# USB-DMX-ISOLATED.net
KiCad netlist of a schematic drawn in EAGLE
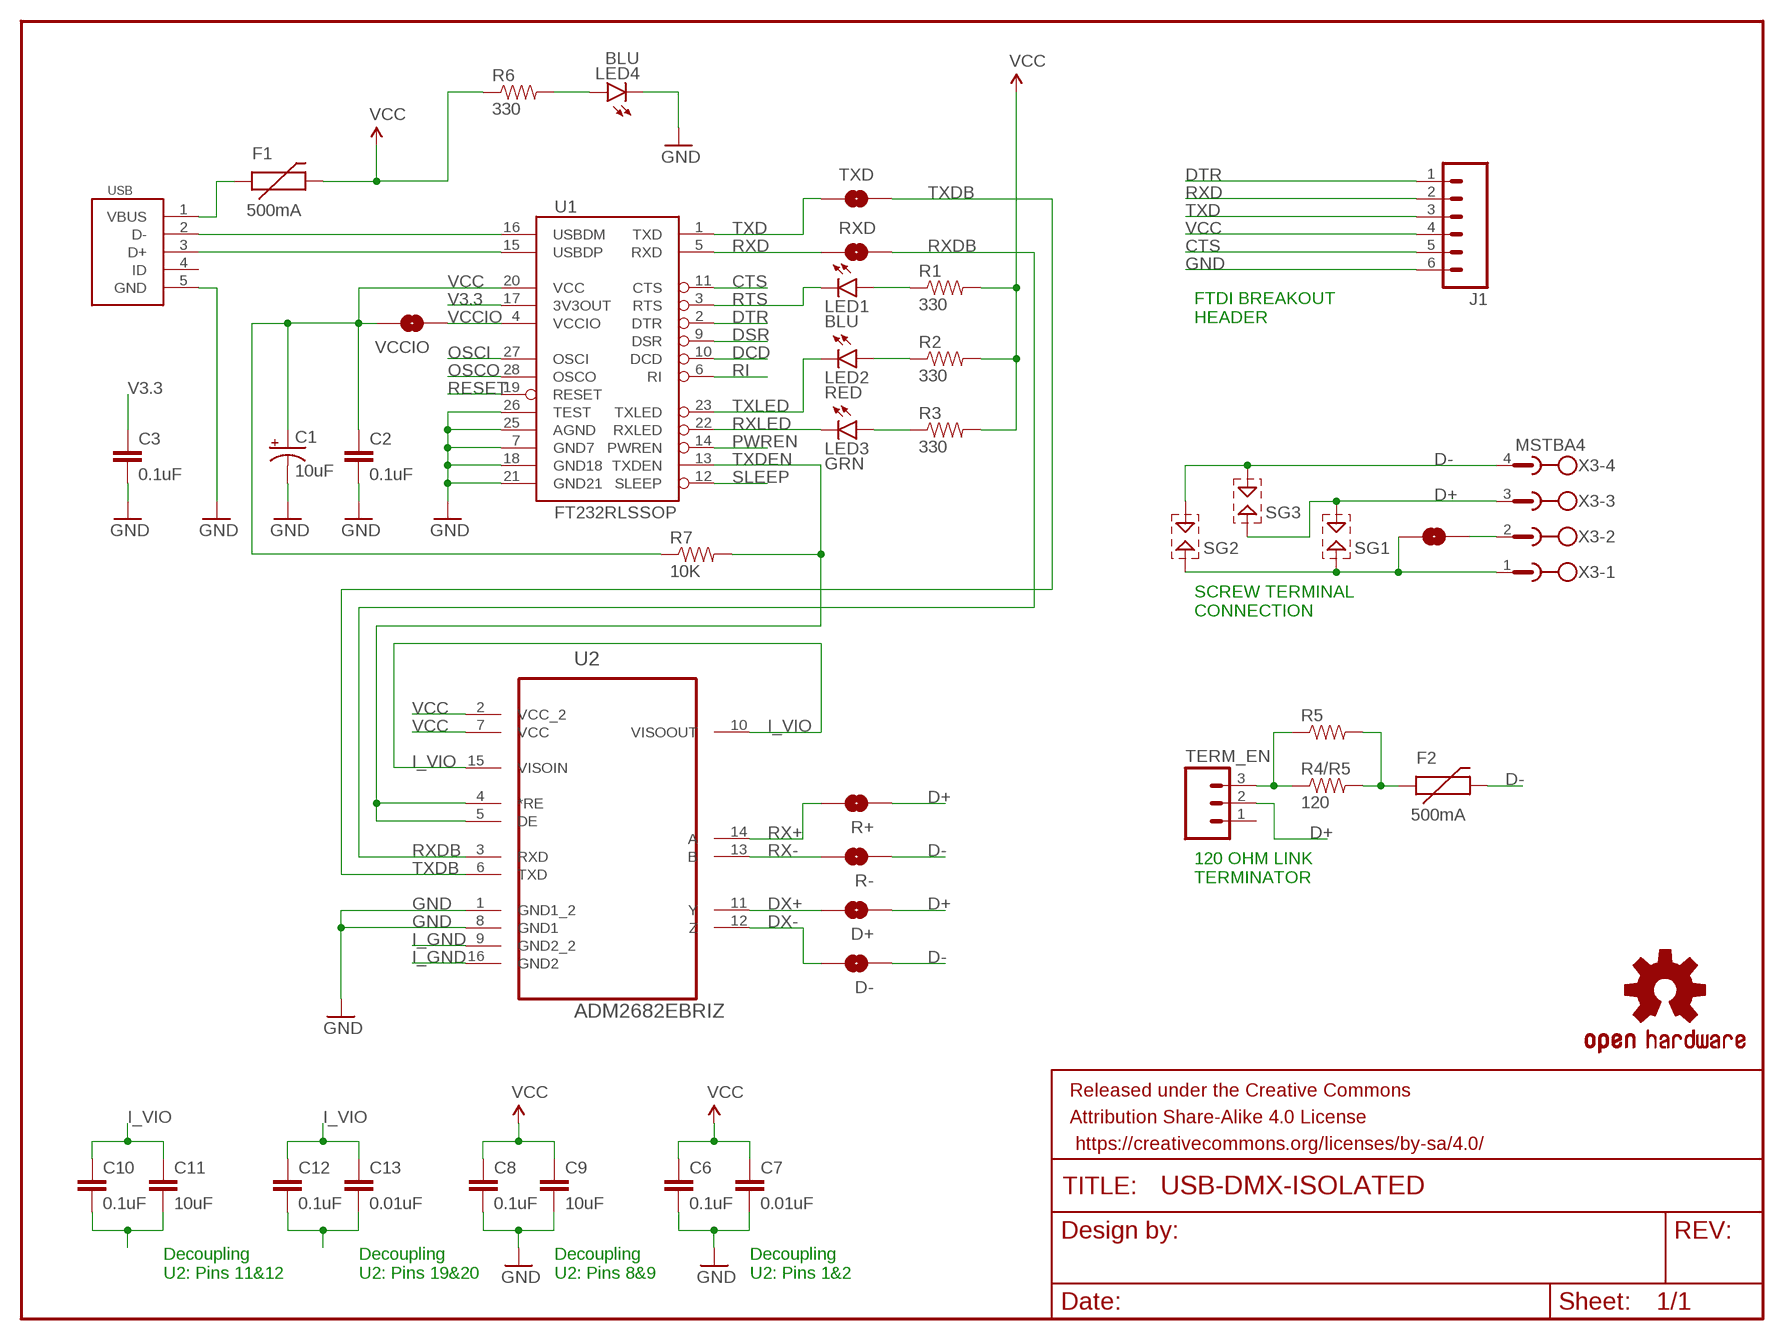
[diagram p0: schematic, sheet 1]

(export (version "E")
  (design (tool "Eeschema 10.0.6"))
  (components
    (comp (ref "C1")
      (value "10uF")
      (footprint "eagle-import:EIA3216")
      (libsource (lib "eagle-import") (part "10UF-16V-10%(TANT)"))
    )
    (comp (ref "C2")
      (value "0.1uF")
      (footprint "eagle-import:1206")
      (libsource (lib "eagle-import") (part "CAP1206"))
    )
    (comp (ref "C3")
      (value "0.1uF")
      (footprint "eagle-import:1206")
      (libsource (lib "eagle-import") (part "CAP1206"))
    )
    (comp (ref "C6")
      (value "0.1uF")
      (footprint "eagle-import:1206")
      (libsource (lib "eagle-import") (part "CAP1206"))
    )
    (comp (ref "C7")
      (value "0.01uF")
      (footprint "eagle-import:1206")
      (libsource (lib "eagle-import") (part "CAP1206"))
    )
    (comp (ref "C8")
      (value "0.1uF")
      (footprint "eagle-import:1206")
      (libsource (lib "eagle-import") (part "CAP1206"))
    )
    (comp (ref "C9")
      (value "10uF")
      (footprint "eagle-import:1206")
      (libsource (lib "eagle-import") (part "CAP1206"))
    )
    (comp (ref "C10")
      (value "0.1uF")
      (footprint "eagle-import:1206")
      (libsource (lib "eagle-import") (part "CAP1206"))
    )
    (comp (ref "C11")
      (value "10uF")
      (footprint "eagle-import:1206")
      (libsource (lib "eagle-import") (part "CAP1206"))
    )
    (comp (ref "C12")
      (value "0.1uF")
      (footprint "eagle-import:1206")
      (libsource (lib "eagle-import") (part "CAP1206"))
    )
    (comp (ref "C13")
      (value "0.01uF")
      (footprint "eagle-import:1206")
      (libsource (lib "eagle-import") (part "CAP1206"))
    )
    (comp (ref "D+")
      (value "SOLDERJUMPERTRACE")
      (footprint "eagle-import:SJ_2S-TRACE")
      (libsource (lib "eagle-import") (part "SOLDERJUMPERTRACE"))
    )
    (comp (ref "D-")
      (value "SOLDERJUMPERTRACE")
      (footprint "eagle-import:SJ_2S-TRACE")
      (libsource (lib "eagle-import") (part "SOLDERJUMPERTRACE"))
    )
    (comp (ref "F1")
      (value "500mA")
      (footprint "eagle-import:PTC-1206")
      (libsource (lib "eagle-import") (part "PTCSMD"))
    )
    (comp (ref "F2")
      (value "500mA")
      (footprint "eagle-import:PTC-1206")
      (libsource (lib "eagle-import") (part "PTCSMD"))
    )
    (comp (ref "FRAME1")
      (value "FRAME-LETTERNO_PACKAGE")
      (footprint "eagle-import:DUMMY")
      (fields (field (name "DESIGNER") "Nobody"))
      (libsource (lib "eagle-import") (part "FRAME-LETTERNO_PACKAGE"))
    )
    (comp (ref "J1")
      (value "M06LOCK")
      (footprint "eagle-import:1X06_LOCK")
      (libsource (lib "eagle-import") (part "M06LOCK"))
    )
    (comp (ref "LED1")
      (value "BLU")
      (footprint "eagle-import:LED-1206")
      (libsource (lib "eagle-import") (part "LED1206"))
    )
    (comp (ref "LED2")
      (value "RED")
      (footprint "eagle-import:LED-1206")
      (libsource (lib "eagle-import") (part "LED1206"))
    )
    (comp (ref "LED3")
      (value "GRN")
      (footprint "eagle-import:LED-1206")
      (libsource (lib "eagle-import") (part "LED1206"))
    )
    (comp (ref "LED4")
      (value "BLU")
      (footprint "eagle-import:LED-1206")
      (libsource (lib "eagle-import") (part "LED1206"))
    )
    (comp (ref "LOGO1")
      (value "OSHW-LOGOS")
      (footprint "eagle-import:OSHW-LOGO-S")
      (libsource (lib "eagle-import") (part "OSHW-LOGOS"))
    )
    (comp (ref "P2_COM")
      (value "SOLDERJUMPERTRACE")
      (footprint "eagle-import:SJ_2S-TRACE")
      (libsource (lib "eagle-import") (part "SOLDERJUMPERTRACE"))
    )
    (comp (ref "R+")
      (value "SOLDERJUMPERTRACE")
      (footprint "eagle-import:SJ_2S-TRACE")
      (libsource (lib "eagle-import") (part "SOLDERJUMPERTRACE"))
    )
    (comp (ref "R-")
      (value "SOLDERJUMPERTRACE")
      (footprint "eagle-import:SJ_2S-TRACE")
      (libsource (lib "eagle-import") (part "SOLDERJUMPERTRACE"))
    )
    (comp (ref "R1")
      (value "330")
      (footprint "eagle-import:1206")
      (libsource (lib "eagle-import") (part "RESISTOR1206"))
    )
    (comp (ref "R2")
      (value "330")
      (footprint "eagle-import:1206")
      (libsource (lib "eagle-import") (part "RESISTOR1206"))
    )
    (comp (ref "R3")
      (value "330")
      (footprint "eagle-import:1206")
      (libsource (lib "eagle-import") (part "RESISTOR1206"))
    )
    (comp (ref "R4/R5")
      (value "120")
      (footprint "eagle-import:1206")
      (libsource (lib "eagle-import") (part "RESISTOR1206"))
    )
    (comp (ref "R5")
      (value "RESISTORPTH-1W")
      (footprint "eagle-import:AXIAL-0.6")
      (libsource (lib "eagle-import") (part "RESISTORPTH-1W"))
    )
    (comp (ref "R6")
      (value "330")
      (footprint "eagle-import:1206")
      (libsource (lib "eagle-import") (part "RESISTOR1206"))
    )
    (comp (ref "R7")
      (value "10K")
      (footprint "eagle-import:1206")
      (libsource (lib "eagle-import") (part "RESISTOR1206"))
    )
    (comp (ref "RXD")
      (value "SOLDERJUMPERTRACE")
      (footprint "eagle-import:SJ_2S-TRACE")
      (libsource (lib "eagle-import") (part "SOLDERJUMPERTRACE"))
    )
    (comp (ref "SG1")
      (value "SPARK-GAP-8")
      (footprint "eagle-import:SPARK-GAP-8")
      (libsource (lib "eagle-import") (part "SPARK-GAP-8"))
    )
    (comp (ref "SG2")
      (value "SPARK-GAP-8")
      (footprint "eagle-import:SPARK-GAP-8")
      (libsource (lib "eagle-import") (part "SPARK-GAP-8"))
    )
    (comp (ref "SG3")
      (value "SPARK-GAP-8")
      (footprint "eagle-import:SPARK-GAP-8")
      (libsource (lib "eagle-import") (part "SPARK-GAP-8"))
    )
    (comp (ref "TERM_EN")
      (value "M03LOCK")
      (footprint "eagle-import:1X03_LOCK")
      (libsource (lib "eagle-import") (part "M03LOCK"))
    )
    (comp (ref "TXD")
      (value "SOLDERJUMPERTRACE")
      (footprint "eagle-import:SJ_2S-TRACE")
      (libsource (lib "eagle-import") (part "SOLDERJUMPERTRACE"))
    )
    (comp (ref "U1")
      (value "FT232RLSSOP")
      (footprint "eagle-import:SSOP28DB")
      (libsource (lib "eagle-import") (part "FT232RLSSOP"))
    )
    (comp (ref "U2")
      (value "ADM2682EBRIZ")
      (footprint "eagle-import:SOIC127P1032X265-16N")
      (libsource (lib "eagle-import") (part "ADM2682EBRIZ"))
    )
    (comp (ref "USB")
      (value "USB-CON-5PIN-105017-0001")
      (footprint "eagle-import:USB-MICRO-MOLEX-105017-0001")
      (libsource (lib "eagle-import") (part "USB-CON-5PIN-105017-0001"))
    )
    (comp (ref "VCCIO")
      (value "SOLDERJUMPERTRACE")
      (footprint "eagle-import:SJ_2S-TRACE")
      (libsource (lib "eagle-import") (part "SOLDERJUMPERTRACE"))
    )
    (comp (ref "X3")
      (value "MSTBA4")
      (footprint "eagle-import:MSTBA4")
      (fields (field (name "MF") "FARNELL") (field (name "MPN") "1757268"))
      (libsource (lib "eagle-import") (part "MSTBA4"))
    )
  )
  (nets
    (net (code "1") (name "/CTS") (class "Default")
      (node (ref "J1") (pin "5") (pinfunction "5_5") (pintype "passive"))
      (node (ref "U1") (pin "11") (pinfunction "CTS_11") (pintype "input"))
    )
    (net (code "2") (name "/D+") (class "Default")
      (node (ref "D+") (pin "1") (pinfunction "1_1") (pintype "passive"))
      (node (ref "R+") (pin "1") (pinfunction "1_1") (pintype "passive"))
      (node (ref "SG1") (pin "1") (pinfunction "1_1") (pintype "passive"))
      (node (ref "SG3") (pin "2") (pinfunction "2_2") (pintype "passive"))
      (node (ref "TERM_EN") (pin "2") (pinfunction "2_2") (pintype "passive"))
      (node (ref "X3") (pin "3") (pinfunction "1_3") (pintype "passive"))
    )
    (net (code "3") (name "/D-") (class "Default")
      (node (ref "D-") (pin "1") (pinfunction "1_1") (pintype "passive"))
      (node (ref "F2") (pin "2") (pinfunction "2_2") (pintype "bidirectional"))
      (node (ref "R-") (pin "1") (pinfunction "1_1") (pintype "passive"))
      (node (ref "SG2") (pin "1") (pinfunction "1_1") (pintype "passive"))
      (node (ref "SG3") (pin "1") (pinfunction "1_1") (pintype "passive"))
      (node (ref "X3") (pin "4") (pinfunction "1_4") (pintype "passive"))
    )
    (net (code "4") (name "/DCD") (class "Default")
      (node (ref "U1") (pin "10") (pinfunction "DCD_10") (pintype "input"))
    )
    (net (code "5") (name "/DSR") (class "Default")
      (node (ref "U1") (pin "9") (pinfunction "DSR_9") (pintype "input"))
    )
    (net (code "6") (name "/DTR") (class "Default")
      (node (ref "J1") (pin "1") (pinfunction "1_1") (pintype "passive"))
      (node (ref "U1") (pin "2") (pinfunction "DTR_2") (pintype "output"))
    )
    (net (code "7") (name "/DX+") (class "Default")
      (node (ref "D+") (pin "2") (pinfunction "2_2") (pintype "passive"))
      (node (ref "U2") (pin "11") (pinfunction "Y_11") (pintype "passive"))
    )
    (net (code "8") (name "/DX-") (class "Default")
      (node (ref "D-") (pin "2") (pinfunction "2_2") (pintype "passive"))
      (node (ref "U2") (pin "12") (pinfunction "Z_12") (pintype "passive"))
    )
    (net (code "9") (name "/I_GND") (class "Default")
      (node (ref "C10") (pin "2") (pinfunction "2_2") (pintype "passive"))
      (node (ref "C11") (pin "2") (pinfunction "2_2") (pintype "passive"))
      (node (ref "C12") (pin "2") (pinfunction "2_2") (pintype "passive"))
      (node (ref "C13") (pin "2") (pinfunction "2_2") (pintype "passive"))
      (node (ref "P2_COM") (pin "1") (pinfunction "1_1") (pintype "passive"))
      (node (ref "SG1") (pin "2") (pinfunction "2_2") (pintype "passive"))
      (node (ref "SG2") (pin "2") (pinfunction "2_2") (pintype "passive"))
      (node (ref "U2") (pin "16") (pinfunction "GND2_16") (pintype "passive"))
      (node (ref "U2") (pin "9") (pinfunction "GND2_2_9") (pintype "passive"))
      (node (ref "X3") (pin "1") (pinfunction "1_1") (pintype "passive"))
    )
    (net (code "10") (name "/I_VIO") (class "Default")
      (node (ref "C10") (pin "1") (pinfunction "1_1") (pintype "passive"))
      (node (ref "C11") (pin "1") (pinfunction "1_1") (pintype "passive"))
      (node (ref "C12") (pin "1") (pinfunction "1_1") (pintype "passive"))
      (node (ref "C13") (pin "1") (pinfunction "1_1") (pintype "passive"))
      (node (ref "U2") (pin "10") (pinfunction "VISOOUT_10") (pintype "passive"))
      (node (ref "U2") (pin "15") (pinfunction "VISOIN_15") (pintype "passive"))
    )
    (net (code "11") (name "/OSCI") (class "Default")
      (node (ref "U1") (pin "27") (pinfunction "OSCI_27") (pintype "input"))
    )
    (net (code "12") (name "/OSCO") (class "Default")
      (node (ref "U1") (pin "28") (pinfunction "OSCO_28") (pintype "output"))
    )
    (net (code "13") (name "/PWREN") (class "Default")
      (node (ref "U1") (pin "14") (pinfunction "PWREN_14") (pintype "input"))
    )
    (net (code "14") (name "/RESET") (class "Default")
      (node (ref "U1") (pin "19") (pinfunction "RESET_19") (pintype "input"))
    )
    (net (code "15") (name "/RI") (class "Default")
      (node (ref "U1") (pin "6") (pinfunction "RI_6") (pintype "input"))
    )
    (net (code "16") (name "/RTS") (class "Default")
      (node (ref "LED1") (pin "C") (pinfunction "C_C") (pintype "passive"))
      (node (ref "U1") (pin "3") (pinfunction "RTS_3") (pintype "output"))
    )
    (net (code "17") (name "/RX+") (class "Default")
      (node (ref "R+") (pin "2") (pinfunction "2_2") (pintype "passive"))
      (node (ref "U2") (pin "14") (pinfunction "A_14") (pintype "passive"))
    )
    (net (code "18") (name "/RX-") (class "Default")
      (node (ref "R-") (pin "2") (pinfunction "2_2") (pintype "passive"))
      (node (ref "U2") (pin "13") (pinfunction "B_13") (pintype "passive"))
    )
    (net (code "19") (name "/RXD") (class "Default")
      (node (ref "J1") (pin "2") (pinfunction "2_2") (pintype "passive"))
      (node (ref "RXD") (pin "1") (pinfunction "1_1") (pintype "passive"))
      (node (ref "U1") (pin "5") (pinfunction "RXD_5") (pintype "input"))
    )
    (net (code "20") (name "/RXDB") (class "Default")
      (node (ref "RXD") (pin "2") (pinfunction "2_2") (pintype "passive"))
      (node (ref "U2") (pin "3") (pinfunction "RXD_3") (pintype "passive"))
    )
    (net (code "21") (name "/RXLED") (class "Default")
      (node (ref "LED3") (pin "C") (pinfunction "C_C") (pintype "passive"))
      (node (ref "U1") (pin "22") (pinfunction "RXLED_22") (pintype "input"))
    )
    (net (code "22") (name "/SLEEP") (class "Default")
      (node (ref "U1") (pin "12") (pinfunction "SLEEP_12") (pintype "input"))
    )
    (net (code "23") (name "/TXD") (class "Default")
      (node (ref "J1") (pin "3") (pinfunction "3_3") (pintype "passive"))
      (node (ref "TXD") (pin "1") (pinfunction "1_1") (pintype "passive"))
      (node (ref "U1") (pin "1") (pinfunction "TXD_1") (pintype "output"))
    )
    (net (code "24") (name "/TXDB") (class "Default")
      (node (ref "TXD") (pin "2") (pinfunction "2_2") (pintype "passive"))
      (node (ref "U2") (pin "6") (pinfunction "TXD_6") (pintype "passive"))
    )
    (net (code "25") (name "/TXDEN") (class "Default")
      (node (ref "R7") (pin "2") (pinfunction "2_2") (pintype "passive"))
      (node (ref "U1") (pin "13") (pinfunction "TXDEN_13") (pintype "input"))
      (node (ref "U2") (pin "4") (pinfunction "*RE_4") (pintype "passive"))
      (node (ref "U2") (pin "5") (pinfunction "DE_5") (pintype "passive"))
    )
    (net (code "26") (name "/TXLED") (class "Default")
      (node (ref "LED2") (pin "C") (pinfunction "C_C") (pintype "passive"))
      (node (ref "U1") (pin "23") (pinfunction "TXLED_23") (pintype "input"))
    )
    (net (code "27") (name "/V3.3") (class "Default")
      (node (ref "C3") (pin "1") (pinfunction "1_1") (pintype "passive"))
      (node (ref "U1") (pin "17") (pinfunction "3V3OUT_17") (pintype "output"))
    )
    (net (code "28") (name "/VCCIO") (class "Default")
      (node (ref "U1") (pin "4") (pinfunction "VCCIO_4") (pintype "power_in"))
      (node (ref "VCCIO") (pin "1") (pinfunction "1_1") (pintype "passive"))
    )
    (net (code "29") (name "GND") (class "Default")
      (node (ref "C1") (pin "C") (pinfunction "-_C") (pintype "passive"))
      (node (ref "C2") (pin "2") (pinfunction "2_2") (pintype "passive"))
      (node (ref "C3") (pin "2") (pinfunction "2_2") (pintype "passive"))
      (node (ref "C6") (pin "2") (pinfunction "2_2") (pintype "passive"))
      (node (ref "C7") (pin "2") (pinfunction "2_2") (pintype "passive"))
      (node (ref "C8") (pin "2") (pinfunction "2_2") (pintype "passive"))
      (node (ref "C9") (pin "2") (pinfunction "2_2") (pintype "passive"))
      (node (ref "J1") (pin "6") (pinfunction "6_6") (pintype "passive"))
      (node (ref "LED4") (pin "C") (pinfunction "C_C") (pintype "passive"))
      (node (ref "U1") (pin "18") (pinfunction "GND18_18") (pintype "power_in"))
      (node (ref "U1") (pin "21") (pinfunction "GND21_21") (pintype "power_in"))
      (node (ref "U1") (pin "25") (pinfunction "AGND_25") (pintype "power_in"))
      (node (ref "U1") (pin "26") (pinfunction "TEST_26") (pintype "input"))
      (node (ref "U1") (pin "7") (pinfunction "GND7_7") (pintype "power_in"))
      (node (ref "U2") (pin "1") (pinfunction "GND1_2_1") (pintype "passive"))
      (node (ref "U2") (pin "8") (pinfunction "GND1_8") (pintype "passive"))
      (node (ref "USB") (pin "5") (pinfunction "GND_5") (pintype "power_in"))
    )
    (net (code "30") (name "Net-(LED1-PadA)") (class "Default")
      (node (ref "LED1") (pin "A") (pinfunction "A_A") (pintype "passive"))
      (node (ref "R1") (pin "1") (pinfunction "1_1") (pintype "passive"))
    )
    (net (code "31") (name "Net-(LED2-PadA)") (class "Default")
      (node (ref "LED2") (pin "A") (pinfunction "A_A") (pintype "passive"))
      (node (ref "R2") (pin "1") (pinfunction "1_1") (pintype "passive"))
    )
    (net (code "32") (name "Net-(LED3-PadA)") (class "Default")
      (node (ref "LED3") (pin "A") (pinfunction "A_A") (pintype "passive"))
      (node (ref "R3") (pin "1") (pinfunction "1_1") (pintype "passive"))
    )
    (net (code "33") (name "Net-(LED4-PadA)") (class "Default")
      (node (ref "LED4") (pin "A") (pinfunction "A_A") (pintype "passive"))
      (node (ref "R6") (pin "2") (pinfunction "2_2") (pintype "passive"))
    )
    (net (code "34") (name "Net-(R5-1)") (class "Default")
      (node (ref "R4/R5") (pin "1") (pinfunction "1_1") (pintype "passive"))
      (node (ref "R5") (pin "P$1") (pinfunction "1_P$1") (pintype "passive"))
      (node (ref "TERM_EN") (pin "3") (pinfunction "3_3") (pintype "passive"))
    )
    (net (code "35") (name "Net-(R5-2)") (class "Default")
      (node (ref "F2") (pin "1") (pinfunction "1_1") (pintype "bidirectional"))
      (node (ref "R4/R5") (pin "2") (pinfunction "2_2") (pintype "passive"))
      (node (ref "R5") (pin "P$2") (pinfunction "2_P$2") (pintype "passive"))
    )
    (net (code "36") (name "Net-(U1-USBDM)") (class "Default")
      (node (ref "U1") (pin "16") (pinfunction "USBDM_16") (pintype "bidirectional"))
      (node (ref "USB") (pin "2") (pinfunction "D-_2") (pintype "bidirectional"))
    )
    (net (code "37") (name "Net-(U1-USBDP)") (class "Default")
      (node (ref "U1") (pin "15") (pinfunction "USBDP_15") (pintype "bidirectional"))
      (node (ref "USB") (pin "3") (pinfunction "D+_3") (pintype "bidirectional"))
    )
    (net (code "38") (name "Net-(USB-VBUS)") (class "Default")
      (node (ref "F1") (pin "1") (pinfunction "1_1") (pintype "bidirectional"))
      (node (ref "USB") (pin "1") (pinfunction "VBUS_1") (pintype "power_in"))
    )
    (net (code "39") (name "Net-(X3B-1)") (class "Default")
      (node (ref "P2_COM") (pin "2") (pinfunction "2_2") (pintype "passive"))
      (node (ref "X3") (pin "2") (pinfunction "1_2") (pintype "passive"))
    )
    (net (code "40") (name "VCC") (class "Default")
      (node (ref "C1") (pin "A") (pinfunction "+_A") (pintype "passive"))
      (node (ref "C2") (pin "1") (pinfunction "1_1") (pintype "passive"))
      (node (ref "C6") (pin "1") (pinfunction "1_1") (pintype "passive"))
      (node (ref "C7") (pin "1") (pinfunction "1_1") (pintype "passive"))
      (node (ref "C8") (pin "1") (pinfunction "1_1") (pintype "passive"))
      (node (ref "C9") (pin "1") (pinfunction "1_1") (pintype "passive"))
      (node (ref "F1") (pin "2") (pinfunction "2_2") (pintype "bidirectional"))
      (node (ref "J1") (pin "4") (pinfunction "4_4") (pintype "passive"))
      (node (ref "R1") (pin "2") (pinfunction "2_2") (pintype "passive"))
      (node (ref "R2") (pin "2") (pinfunction "2_2") (pintype "passive"))
      (node (ref "R3") (pin "2") (pinfunction "2_2") (pintype "passive"))
      (node (ref "R6") (pin "1") (pinfunction "1_1") (pintype "passive"))
      (node (ref "R7") (pin "1") (pinfunction "1_1") (pintype "passive"))
      (node (ref "U1") (pin "20") (pinfunction "VCC_20") (pintype "power_in"))
      (node (ref "U2") (pin "2") (pinfunction "VCC_2_2") (pintype "passive"))
      (node (ref "U2") (pin "7") (pinfunction "VCC_7") (pintype "passive"))
      (node (ref "VCCIO") (pin "2") (pinfunction "2_2") (pintype "passive"))
    )
    (net (code "41") (name "unconnected-(TERM_EN-Pad1)") (class "Default")
      (node (ref "TERM_EN") (pin "1") (pinfunction "1_1") (pintype "passive"))
    )
    (net (code "42") (name "unconnected-(USB-ID-Pad4)") (class "Default")
      (node (ref "USB") (pin "4") (pinfunction "ID_4") (pintype "bidirectional"))
    )
  )
)
